# 11_-_Power_Input_and_Regulators.net
KiCad netlist of a schematic drawn in Altium Designer
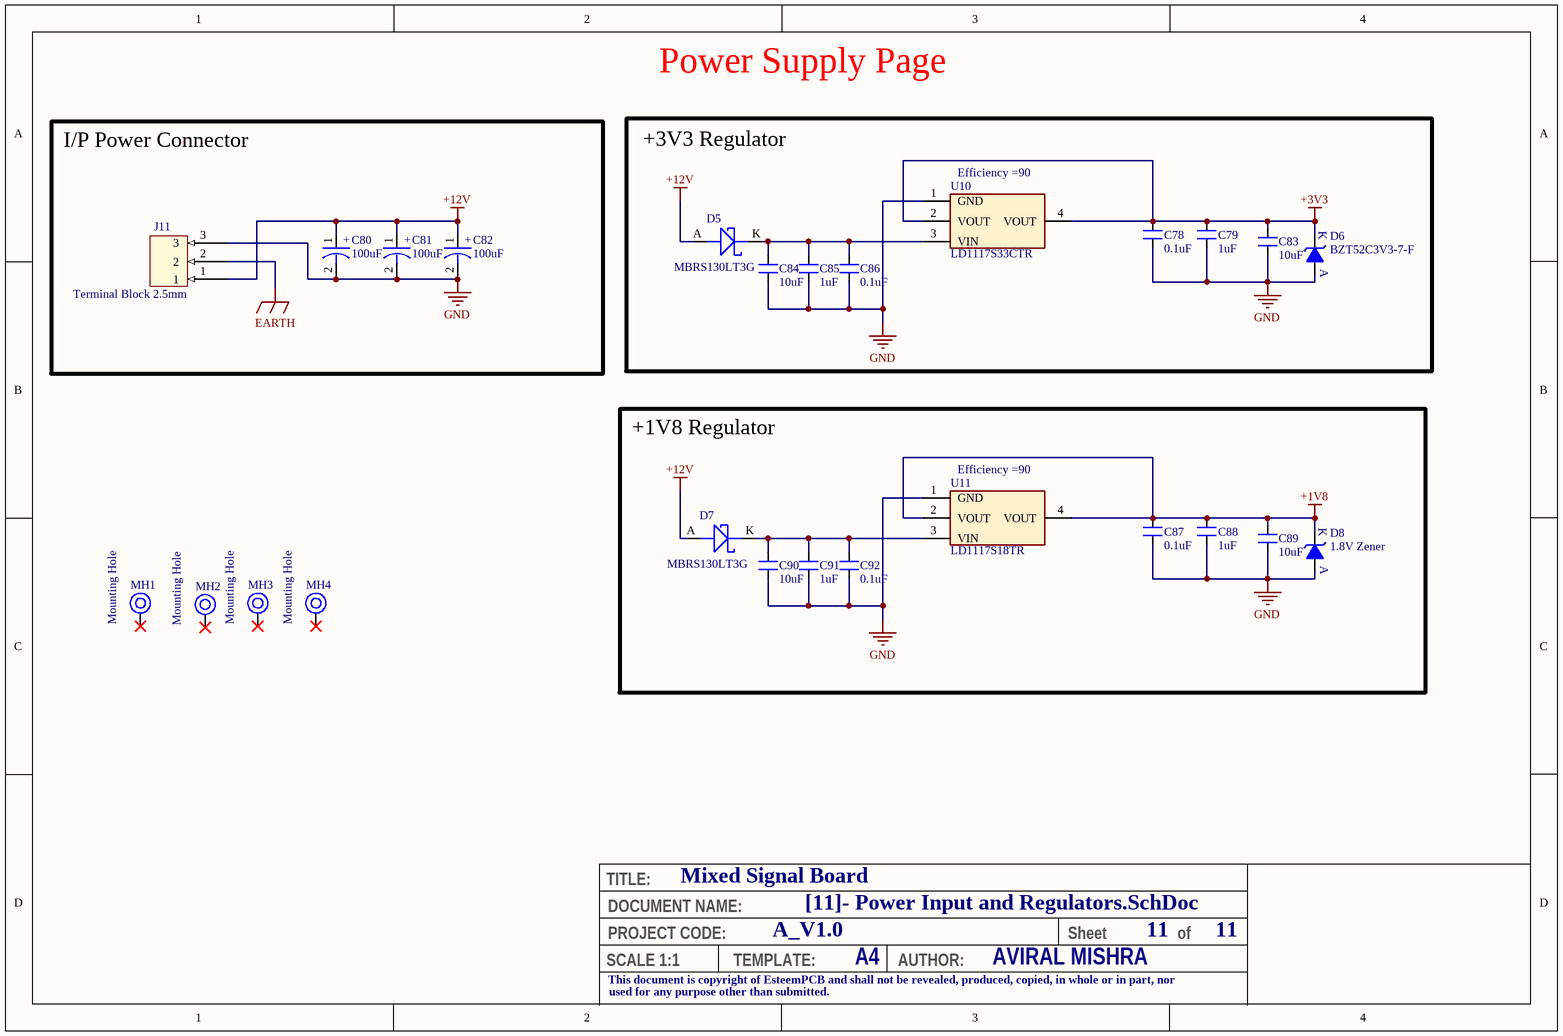
[diagram p0: [11]- Power Input and Regulators.SchDoc]

(export (version "E")
  (design (tool "Eeschema 10.0.6"))
  (components
    (comp (ref "C78")
      (value "0.1uF")
      (footprint "CAP_0805")
      (description "0.1µF ±10% 50V Ceramic Capacitor X7R 0805 (2012 Metric)")
      (fields
        (field (name "MANUFACTURER") "Samsung")
        (field (name "MANUFACTURER PART NUMBER") "CL21B104KBCNNNC")
      )
      (libsource (lib "ESTEEMPCBLIB") (part "CAP_0.1uF-50V-10%-0805"))
    )
    (comp (ref "C79")
      (value "1uF")
      (footprint "CAP_0805")
      (description "1µF ±5% 50V Ceramic Capacitor X7R 0805 (2012 Metric)")
      (fields
        (field (name "MANUFACTURER") "Samsung")
        (field (name "MANUFACTURER PART NUMBER") "CC0805JKX7R9BB105")
      )
      (libsource (lib "ESTEEMPCBLIB") (part "CAP_1uF-50V-5%-0805"))
    )
    (comp (ref "C80")
      (value "100uF")
      (footprint "ACAP_P305_D393_H393_RAD")
      (description "100µF 50V Aluminum Polymer Capacitor Radial, Can - SMD 28mOhm 4000 Hrs @ 125°C")
      (fields
        (field (name "MANUFACTURER") "Nichicon")
        (field (name "MANUFACTURER PART NUMBER") "GYA1H101MCQ1GS")
      )
      (libsource (lib "ESTEEMPCBLIB") (part "CAP-P_100uF-50V-20%-RAD"))
    )
    (comp (ref "C81")
      (value "100uF")
      (footprint "ACAP_P305_D393_H393_RAD")
      (description "100µF 50V Aluminum Polymer Capacitor Radial, Can - SMD 28mOhm 4000 Hrs @ 125°C")
      (fields
        (field (name "MANUFACTURER") "Nichicon")
        (field (name "MANUFACTURER PART NUMBER") "GYA1H101MCQ1GS")
      )
      (libsource (lib "ESTEEMPCBLIB") (part "CAP-P_100uF-50V-20%-RAD"))
    )
    (comp (ref "C82")
      (value "100uF")
      (footprint "ACAP_P305_D393_H393_RAD")
      (description "100µF 50V Aluminum Polymer Capacitor Radial, Can - SMD 28mOhm 4000 Hrs @ 125°C")
      (fields
        (field (name "MANUFACTURER") "Nichicon")
        (field (name "MANUFACTURER PART NUMBER") "GYA1H101MCQ1GS")
      )
      (libsource (lib "ESTEEMPCBLIB") (part "CAP-P_100uF-50V-20%-RAD"))
    )
    (comp (ref "C83")
      (value "10uF")
      (footprint "CAP_1206")
      (description "10µF ±10% 50V Ceramic Capacitor X7R 1206 (3216 Metric)")
      (fields
        (field (name "MANUFACTURER") "KEMET")
        (field (name "MANUFACTURER PART NUMBER") "CL31B106KBHNNNE")
      )
      (libsource (lib "ESTEEMPCBLIB") (part "CAP_10uF-50V-10%-1206"))
    )
    (comp (ref "C84")
      (value "10uF")
      (footprint "CAP_1206")
      (description "10µF ±10% 50V Ceramic Capacitor X7R 1206 (3216 Metric)")
      (fields
        (field (name "MANUFACTURER") "KEMET")
        (field (name "MANUFACTURER PART NUMBER") "CL31B106KBHNNNE")
      )
      (libsource (lib "ESTEEMPCBLIB") (part "CAP_10uF-50V-10%-1206"))
    )
    (comp (ref "C85")
      (value "1uF")
      (footprint "CAP_0805")
      (description "1µF ±5% 50V Ceramic Capacitor X7R 0805 (2012 Metric)")
      (fields
        (field (name "MANUFACTURER") "Samsung")
        (field (name "MANUFACTURER PART NUMBER") "CC0805JKX7R9BB105")
      )
      (libsource (lib "ESTEEMPCBLIB") (part "CAP_1uF-50V-5%-0805"))
    )
    (comp (ref "C86")
      (value "0.1uF")
      (footprint "CAP_0805")
      (description "0.1µF ±10% 50V Ceramic Capacitor X7R 0805 (2012 Metric)")
      (fields
        (field (name "MANUFACTURER") "Samsung")
        (field (name "MANUFACTURER PART NUMBER") "CL21B104KBCNNNC")
      )
      (libsource (lib "ESTEEMPCBLIB") (part "CAP_0.1uF-50V-10%-0805"))
    )
    (comp (ref "C87")
      (value "0.1uF")
      (footprint "CAP_0805")
      (description "0.1µF ±10% 50V Ceramic Capacitor X7R 0805 (2012 Metric)")
      (fields
        (field (name "MANUFACTURER") "Samsung")
        (field (name "MANUFACTURER PART NUMBER") "CL21B104KBCNNNC")
      )
      (libsource (lib "ESTEEMPCBLIB") (part "CAP_0.1uF-50V-10%-0805"))
    )
    (comp (ref "C88")
      (value "1uF")
      (footprint "CAP_0805")
      (description "1µF ±5% 50V Ceramic Capacitor X7R 0805 (2012 Metric)")
      (fields
        (field (name "MANUFACTURER") "Samsung")
        (field (name "MANUFACTURER PART NUMBER") "CC0805JKX7R9BB105")
      )
      (libsource (lib "ESTEEMPCBLIB") (part "CAP_1uF-50V-5%-0805"))
    )
    (comp (ref "C89")
      (value "10uF")
      (footprint "CAP_1206")
      (description "10µF ±10% 50V Ceramic Capacitor X7R 1206 (3216 Metric)")
      (fields
        (field (name "MANUFACTURER") "KEMET")
        (field (name "MANUFACTURER PART NUMBER") "CL31B106KBHNNNE")
      )
      (libsource (lib "ESTEEMPCBLIB") (part "CAP_10uF-50V-10%-1206"))
    )
    (comp (ref "C90")
      (value "10uF")
      (footprint "CAP_1206")
      (description "10µF ±10% 50V Ceramic Capacitor X7R 1206 (3216 Metric)")
      (fields
        (field (name "MANUFACTURER") "KEMET")
        (field (name "MANUFACTURER PART NUMBER") "CL31B106KBHNNNE")
      )
      (libsource (lib "ESTEEMPCBLIB") (part "CAP_10uF-50V-10%-1206"))
    )
    (comp (ref "C91")
      (value "1uF")
      (footprint "CAP_0805")
      (description "1µF ±5% 50V Ceramic Capacitor X7R 0805 (2012 Metric)")
      (fields
        (field (name "MANUFACTURER") "Samsung")
        (field (name "MANUFACTURER PART NUMBER") "CC0805JKX7R9BB105")
      )
      (libsource (lib "ESTEEMPCBLIB") (part "CAP_1uF-50V-5%-0805"))
    )
    (comp (ref "C92")
      (value "0.1uF")
      (footprint "CAP_0805")
      (description "0.1µF ±10% 50V Ceramic Capacitor X7R 0805 (2012 Metric)")
      (fields
        (field (name "MANUFACTURER") "Samsung")
        (field (name "MANUFACTURER PART NUMBER") "CL21B104KBCNNNC")
      )
      (libsource (lib "ESTEEMPCBLIB") (part "CAP_0.1uF-50V-10%-0805"))
    )
    (comp (ref "D5")
      (value "MBRS130LT3G")
      (footprint "DIO_SMB_DO-214AA")
      (description "Diode Schottky 30V 2A Surface Mount SMB")
      (fields (field (name "MANUFACTURER") "ON Semiconductor"))
      (libsource (lib "ESTEEMPCBLIB") (part "DIO-S_445mV-30V-2A-SMB"))
    )
    (comp (ref "D6")
      (value "BZT52C3V3-7-F")
      (footprint "DIO_SOD-123")
      (description "Zener Diode 3.3V 500mW ±6% Surface Mount SOD-123")
      (fields (field (name "MANUFACTURER") "Diodes Incorporated"))
      (libsource (lib "ESTEEMPCBLIB") (part "DIO-Z_3.3V-500mW-SOD123"))
    )
    (comp (ref "D7")
      (value "MBRS130LT3G")
      (footprint "DIO_SMB_DO-214AA")
      (description "Diode Schottky 30V 2A Surface Mount SMB")
      (fields (field (name "MANUFACTURER") "ON Semiconductor"))
      (libsource (lib "ESTEEMPCBLIB") (part "DIO-S_445mV-30V-2A-SMB"))
    )
    (comp (ref "D8")
      (value "1.8V Zener")
      (footprint "DIO_DO-213AB_SMD")
      (description "Zener Diode 1.8V 500mW ±5% Surface Mount DO-213AA")
      (libsource (lib "ESTEEMPCBLIB") (part "DIO-Z_1.8V-500mW-DO213AA"))
    )
    (comp (ref "J11")
      (value "Terminal Block 2.5mm")
      (footprint "CON3_100_TB_TH_ST")
      (description "3 Pins, 1 Row 2.54mm Pitch, straight Connector, male")
      (fields
        (field (name "MANUFACTURER PART NUMBER") "1725669")
        (field (name "MANUFACTURER") "Phoenix Contact")
      )
      (libsource (lib "ESTEEMPCBLIB") (part "CON-TB_3X1-100-ST-TH"))
    )
    (comp (ref "MH1")
      (value "Mounting Hole")
      (footprint "MOUNTING")
      (fields (field (name "MANUFACTURER PART NUMBER") "NA"))
      (libsource (lib "ESTEEMPCBLIB") (part "MH_3.5H_6D"))
    )
    (comp (ref "MH2")
      (value "Mounting Hole")
      (footprint "MOUNTING")
      (fields (field (name "MANUFACTURER PART NUMBER") "NA"))
      (libsource (lib "ESTEEMPCBLIB") (part "MH_3.5H_6D"))
    )
    (comp (ref "MH3")
      (value "Mounting Hole")
      (footprint "MOUNTING")
      (fields (field (name "MANUFACTURER PART NUMBER") "NA"))
      (libsource (lib "ESTEEMPCBLIB") (part "MH_3.5H_6D"))
    )
    (comp (ref "MH4")
      (value "Mounting Hole")
      (footprint "MOUNTING")
      (fields (field (name "MANUFACTURER PART NUMBER") "NA"))
      (libsource (lib "ESTEEMPCBLIB") (part "MH_3.5H_6D"))
    )
    (comp (ref "U10")
      (value "LD1117S33CTR")
      (footprint "SOT223_3")
      (description "Linear Voltage Regulator IC 1 Output 800mA SOT-223")
      (fields (field (name "MANUFACTURER") "STMicroelectronics"))
      (libsource (lib "ESTEEMPCBLIB") (part "REG_15V-3.3V-0.9A-12W-SOT223"))
    )
    (comp (ref "U11")
      (value "LD1117S18TR")
      (footprint "SOT223_3")
      (description "LDO Voltage Regulators 1.8V 0.8A Positive")
      (fields (field (name "MANUFACTURER") "STMicroelectronics"))
      (libsource (lib "ESTEEMPCBLIB") (part "REG_15V-1.8V-0.8A-1.4W-SOT223"))
    )
  )
  (nets
    (net (code "1") (name "+1V8") (class "Default")
      (node (ref "C87") (pin "2") (pinfunction "2_2") (pintype "passive"))
      (node (ref "C88") (pin "2") (pinfunction "2_2") (pintype "passive"))
      (node (ref "C89") (pin "2") (pinfunction "2_2") (pintype "passive"))
      (node (ref "D8") (pin "K") (pinfunction "K_K") (pintype "passive"))
      (node (ref "U11") (pin "2") (pinfunction "VOUT_2") (pintype "passive"))
      (node (ref "U11") (pin "4") (pinfunction "VOUT_4") (pintype "passive"))
    )
    (net (code "2") (name "+3V3") (class "Default")
      (node (ref "C78") (pin "2") (pinfunction "2_2") (pintype "passive"))
      (node (ref "C79") (pin "2") (pinfunction "2_2") (pintype "passive"))
      (node (ref "C83") (pin "2") (pinfunction "2_2") (pintype "passive"))
      (node (ref "D6") (pin "K") (pinfunction "K_K") (pintype "passive"))
      (node (ref "U10") (pin "2") (pinfunction "VOUT_2") (pintype "passive"))
      (node (ref "U10") (pin "4") (pinfunction "VOUT_4") (pintype "passive"))
    )
    (net (code "3") (name "+12V") (class "Default")
      (node (ref "C80") (pin "1") (pinfunction "1_1") (pintype "passive"))
      (node (ref "C81") (pin "1") (pinfunction "1_1") (pintype "passive"))
      (node (ref "C82") (pin "1") (pinfunction "1_1") (pintype "passive"))
      (node (ref "D5") (pin "A") (pinfunction "A_A") (pintype "passive"))
      (node (ref "D7") (pin "A") (pinfunction "A_A") (pintype "passive"))
      (node (ref "J11") (pin "1") (pinfunction "1_1") (pintype "input"))
    )
    (net (code "4") (name "EARTH") (class "Default")
      (node (ref "J11") (pin "2") (pinfunction "2_2") (pintype "input"))
    )
    (net (code "5") (name "GND") (class "Default")
      (node (ref "C78") (pin "1") (pinfunction "1_1") (pintype "passive"))
      (node (ref "C79") (pin "1") (pinfunction "1_1") (pintype "passive"))
      (node (ref "C80") (pin "2") (pinfunction "2_2") (pintype "passive"))
      (node (ref "C81") (pin "2") (pinfunction "2_2") (pintype "passive"))
      (node (ref "C82") (pin "2") (pinfunction "2_2") (pintype "passive"))
      (node (ref "C83") (pin "1") (pinfunction "1_1") (pintype "passive"))
      (node (ref "C84") (pin "1") (pinfunction "1_1") (pintype "passive"))
      (node (ref "C85") (pin "1") (pinfunction "1_1") (pintype "passive"))
      (node (ref "C86") (pin "1") (pinfunction "1_1") (pintype "passive"))
      (node (ref "C87") (pin "1") (pinfunction "1_1") (pintype "passive"))
      (node (ref "C88") (pin "1") (pinfunction "1_1") (pintype "passive"))
      (node (ref "C89") (pin "1") (pinfunction "1_1") (pintype "passive"))
      (node (ref "C90") (pin "1") (pinfunction "1_1") (pintype "passive"))
      (node (ref "C91") (pin "1") (pinfunction "1_1") (pintype "passive"))
      (node (ref "C92") (pin "1") (pinfunction "1_1") (pintype "passive"))
      (node (ref "D6") (pin "A") (pinfunction "A_A") (pintype "passive"))
      (node (ref "D8") (pin "A") (pinfunction "A_A") (pintype "passive"))
      (node (ref "J11") (pin "3") (pinfunction "3_3") (pintype "input"))
      (node (ref "U10") (pin "1") (pinfunction "GND_1") (pintype "passive"))
      (node (ref "U11") (pin "1") (pinfunction "GND_1") (pintype "passive"))
    )
    (net (code "6") (name "Net-(U10-VIN)") (class "Default")
      (node (ref "C84") (pin "2") (pinfunction "2_2") (pintype "passive"))
      (node (ref "C85") (pin "2") (pinfunction "2_2") (pintype "passive"))
      (node (ref "C86") (pin "2") (pinfunction "2_2") (pintype "passive"))
      (node (ref "D5") (pin "K") (pinfunction "K_K") (pintype "passive"))
      (node (ref "U10") (pin "3") (pinfunction "VIN_3") (pintype "passive"))
    )
    (net (code "7") (name "Net-(U11-VIN)") (class "Default")
      (node (ref "C90") (pin "2") (pinfunction "2_2") (pintype "passive"))
      (node (ref "C91") (pin "2") (pinfunction "2_2") (pintype "passive"))
      (node (ref "C92") (pin "2") (pinfunction "2_2") (pintype "passive"))
      (node (ref "D7") (pin "K") (pinfunction "K_K") (pintype "passive"))
      (node (ref "U11") (pin "3") (pinfunction "VIN_3") (pintype "passive"))
    )
    (net (code "8") (name "unconnected-(MH1-Pad1)") (class "Default")
      (node (ref "MH1") (pin "1") (pinfunction "1_1") (pintype "passive+no_connect"))
    )
    (net (code "9") (name "unconnected-(MH2-Pad1)") (class "Default")
      (node (ref "MH2") (pin "1") (pinfunction "1_1") (pintype "passive+no_connect"))
    )
    (net (code "10") (name "unconnected-(MH3-Pad1)") (class "Default")
      (node (ref "MH3") (pin "1") (pinfunction "1_1") (pintype "passive+no_connect"))
    )
    (net (code "11") (name "unconnected-(MH4-Pad1)") (class "Default")
      (node (ref "MH4") (pin "1") (pinfunction "1_1") (pintype "passive+no_connect"))
    )
  )
)
